# rfid_module.net
KiCad netlist of a schematic drawn in EAGLE
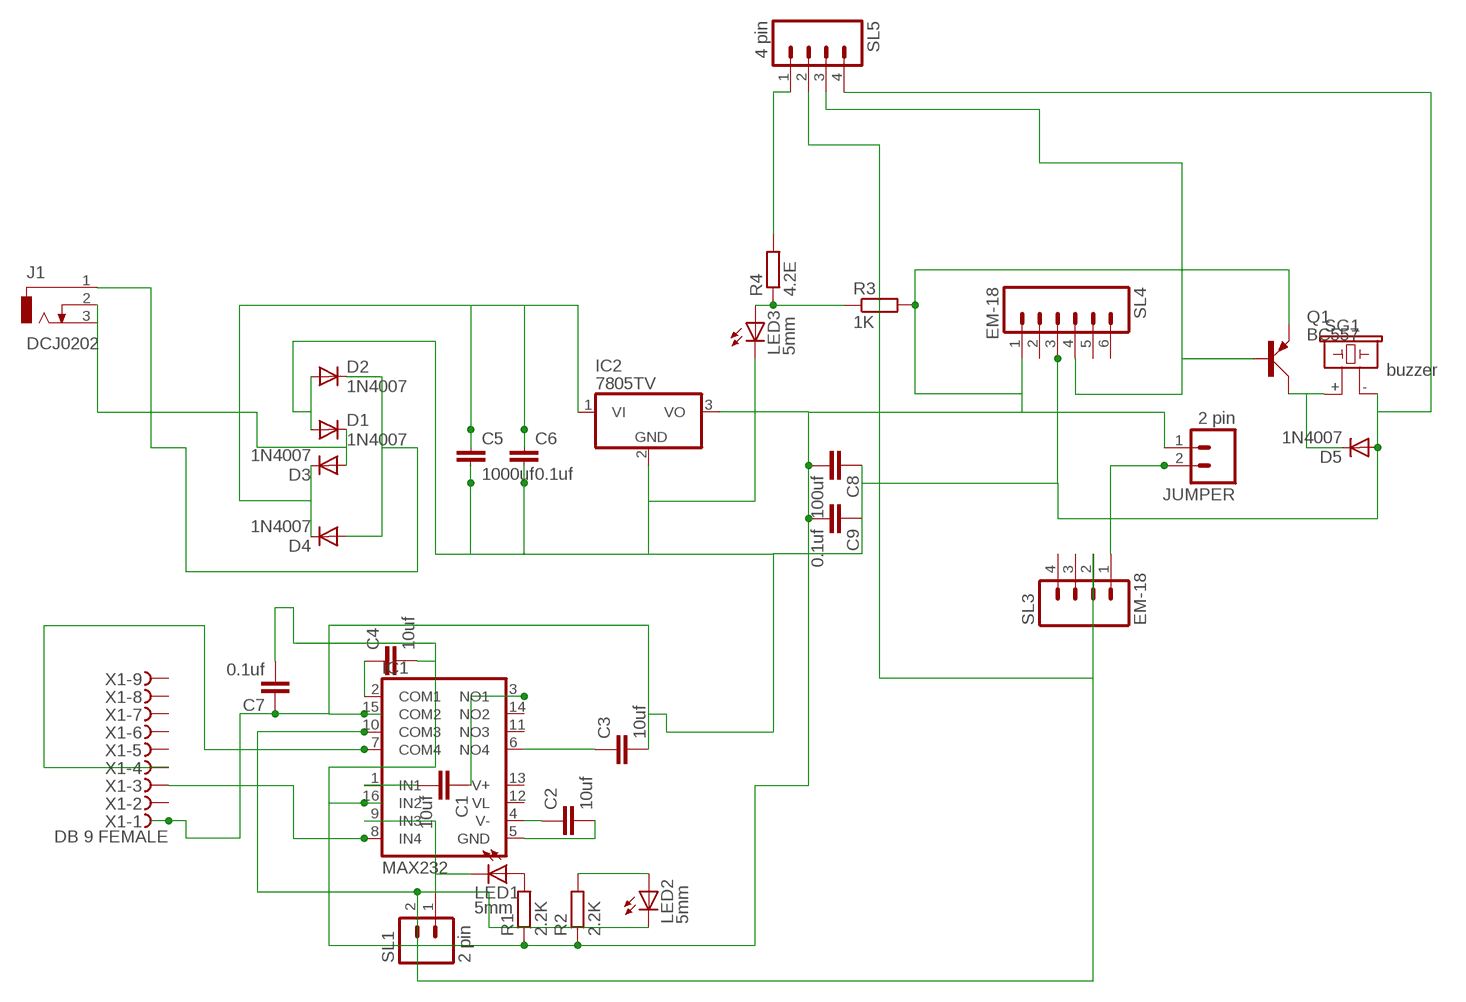
[diagram p0: schematic, sheet 1]

(export (version "E")
  (design (tool "Eeschema 10.0.6"))
  (components
    (comp (ref "C1")
      (value "10uf")
      (footprint "eagle-import:C2.5-3")
      (libsource (lib "eagle-import") (part "C2,5-3"))
    )
    (comp (ref "C2")
      (value "10uf")
      (footprint "eagle-import:C2.5-3")
      (libsource (lib "eagle-import") (part "C2,5-3"))
    )
    (comp (ref "C3")
      (value "10uf")
      (footprint "eagle-import:C2.5-3")
      (libsource (lib "eagle-import") (part "C2,5-3"))
    )
    (comp (ref "C4")
      (value "10uf")
      (footprint "eagle-import:C2.5-3")
      (libsource (lib "eagle-import") (part "C2,5-3"))
    )
    (comp (ref "C5")
      (value "1000uf")
      (footprint "eagle-import:C5B7.2")
      (libsource (lib "eagle-import") (part "C5/7.2"))
    )
    (comp (ref "C6")
      (value "0.1uf")
      (footprint "eagle-import:C2.5-3")
      (libsource (lib "eagle-import") (part "C2,5-3"))
    )
    (comp (ref "C7")
      (value "0.1uf")
      (footprint "eagle-import:C2.5-3")
      (libsource (lib "eagle-import") (part "C2,5-3"))
    )
    (comp (ref "C8")
      (value "100uf")
      (footprint "eagle-import:C2.5-3")
      (libsource (lib "eagle-import") (part "C2,5-3"))
    )
    (comp (ref "C9")
      (value "0.1uf")
      (footprint "eagle-import:C2.5-3")
      (libsource (lib "eagle-import") (part "C2,5-3"))
    )
    (comp (ref "D1")
      (value "1N4007")
      (footprint "eagle-import:DO41-10")
      (libsource (lib "eagle-import") (part "1N4004"))
    )
    (comp (ref "D2")
      (value "1N4007")
      (footprint "eagle-import:DO41-10")
      (libsource (lib "eagle-import") (part "1N4004"))
    )
    (comp (ref "D3")
      (value "1N4007")
      (footprint "eagle-import:DO41-10")
      (libsource (lib "eagle-import") (part "1N4004"))
    )
    (comp (ref "D4")
      (value "1N4007")
      (footprint "eagle-import:DO41-10")
      (libsource (lib "eagle-import") (part "1N4004"))
    )
    (comp (ref "D5")
      (value "1N4007")
      (footprint "eagle-import:DO41-10")
      (libsource (lib "eagle-import") (part "1N4004"))
    )
    (comp (ref "IC1")
      (value "MAX232")
      (footprint "eagle-import:DIL16")
      (fields (field (name "MPN") "MAX313EPE+"))
      (libsource (lib "eagle-import") (part "MAX313PEE"))
    )
    (comp (ref "IC2")
      (value "7805TV")
      (footprint "eagle-import:TO220V")
      (libsource (lib "eagle-import") (part "78TV05"))
    )
    (comp (ref "J1")
      (value "DCJ0202")
      (footprint "eagle-import:DCJ0202")
      (libsource (lib "eagle-import") (part "DCJ0202"))
    )
    (comp (ref "JUMPER")
      (value "2 pin")
      (footprint "eagle-import:02P")
      (libsource (lib "eagle-import") (part "M02"))
    )
    (comp (ref "LED1")
      (value "5mm")
      (footprint "eagle-import:LED5MM")
      (libsource (lib "eagle-import") (part "LED5MM"))
    )
    (comp (ref "LED2")
      (value "5mm")
      (footprint "eagle-import:LED5MM")
      (libsource (lib "eagle-import") (part "LED5MM"))
    )
    (comp (ref "LED3")
      (value "5mm")
      (footprint "eagle-import:LED5MM")
      (libsource (lib "eagle-import") (part "LED5MM"))
    )
    (comp (ref "Q1")
      (value "BC557")
      (footprint "eagle-import:SOT54A")
      (libsource (lib "eagle-import") (part "BC557"))
    )
    (comp (ref "R1")
      (value "2.2K")
      (footprint "eagle-import:0204_7")
      (libsource (lib "eagle-import") (part "R-EU_0204/7"))
    )
    (comp (ref "R2")
      (value "2.2K")
      (footprint "eagle-import:0204_7")
      (libsource (lib "eagle-import") (part "R-EU_0204/7"))
    )
    (comp (ref "R3")
      (value "1K")
      (footprint "eagle-import:0204_7")
      (libsource (lib "eagle-import") (part "R-EU_0204/7"))
    )
    (comp (ref "R4")
      (value "4.2E")
      (footprint "eagle-import:0204_7")
      (libsource (lib "eagle-import") (part "R-EU_0204/7"))
    )
    (comp (ref "SG1")
      (value "buzzer")
      (footprint "eagle-import:F_CM12P")
      (libsource (lib "eagle-import") (part "F/CM12P"))
    )
    (comp (ref "SL1")
      (value "2 pin")
      (footprint "eagle-import:02P")
      (libsource (lib "eagle-import") (part "M02"))
    )
    (comp (ref "SL3")
      (value "EM-18")
      (footprint "eagle-import:04P")
      (libsource (lib "eagle-import") (part "M04"))
    )
    (comp (ref "SL4")
      (value "EM-18")
      (footprint "eagle-import:06P")
      (libsource (lib "eagle-import") (part "M06"))
    )
    (comp (ref "SL5")
      (value "4 pin")
      (footprint "eagle-import:04P")
      (fields (field (name "OC_FARNELL") "unknown") (field (name "OC_NEWARK") "unknown"))
      (libsource (lib "eagle-import") (part "M04"))
    )
    (comp (ref "X1")
      (value "DB 9 FEMALE")
      (footprint "eagle-import:H2M09ST")
      (libsource (lib "eagle-import") (part "D-SUB9-H2M09ST"))
    )
  )
  (nets
    (net (code "1") (name "/V+") (class "Default")
      (node (ref "IC1") (pin "13") (pinfunction "V+_13") (pintype "power_in"))
    )
    (net (code "2") (name "/VL") (class "Default")
      (node (ref "IC1") (pin "12") (pinfunction "VL_12") (pintype "power_in"))
    )
    (net (code "3") (name "Net-(D1-PadC)") (class "Default")
      (node (ref "D1") (pin "C") (pinfunction "C_C") (pintype "passive"))
      (node (ref "D3") (pin "A") (pinfunction "A_A") (pintype "passive"))
      (node (ref "J1") (pin "2") (pinfunction "2_2") (pintype "passive"))
      (node (ref "J1") (pin "3") (pinfunction "3_3") (pintype "passive"))
    )
    (net (code "4") (name "Net-(D2-PadC)") (class "Default")
      (node (ref "D2") (pin "C") (pinfunction "C_C") (pintype "passive"))
      (node (ref "D4") (pin "A") (pinfunction "A_A") (pintype "passive"))
      (node (ref "J1") (pin "1") (pinfunction "1_1") (pintype "passive"))
    )
    (net (code "5") (name "Net-(IC1-COM1)") (class "Default")
      (node (ref "C4") (pin "1") (pinfunction "1_1") (pintype "passive"))
      (node (ref "IC1") (pin "2") (pinfunction "COM1_2") (pintype "passive"))
    )
    (net (code "6") (name "Net-(IC1-COM2)") (class "Default")
      (node (ref "C3") (pin "2") (pinfunction "2_2") (pintype "passive"))
      (node (ref "C5") (pin "2") (pinfunction "2_2") (pintype "passive"))
      (node (ref "C6") (pin "2") (pinfunction "2_2") (pintype "passive"))
      (node (ref "C7") (pin "1") (pinfunction "1_1") (pintype "passive"))
      (node (ref "C8") (pin "1") (pinfunction "1_1") (pintype "passive"))
      (node (ref "C9") (pin "1") (pinfunction "1_1") (pintype "passive"))
      (node (ref "D1") (pin "A") (pinfunction "A_A") (pintype "passive"))
      (node (ref "D2") (pin "A") (pinfunction "A_A") (pintype "passive"))
      (node (ref "D5") (pin "A") (pinfunction "A_A") (pintype "passive"))
      (node (ref "IC1") (pin "15") (pinfunction "COM2_15") (pintype "passive"))
      (node (ref "IC2") (pin "2") (pinfunction "GND_2") (pintype "passive"))
      (node (ref "LED3") (pin "K") (pinfunction "C_K") (pintype "passive"))
      (node (ref "SG1") (pin "-") (pinfunction "2_-") (pintype "passive"))
      (node (ref "SL4") (pin "3") (pinfunction "3_3") (pintype "passive"))
      (node (ref "SL5") (pin "4") (pinfunction "4_4") (pintype "passive"))
      (node (ref "X1") (pin "1") (pinfunction "F_1") (pintype "passive"))
    )
    (net (code "7") (name "Net-(IC1-COM3)") (class "Default")
      (node (ref "IC1") (pin "10") (pinfunction "COM3_10") (pintype "passive"))
      (node (ref "LED2") (pin "K") (pinfunction "C_K") (pintype "passive"))
      (node (ref "SL1") (pin "2") (pinfunction "2_2") (pintype "passive"))
      (node (ref "SL3") (pin "2") (pinfunction "2_2") (pintype "passive"))
      (node (ref "SL5") (pin "2") (pinfunction "2_2") (pintype "passive"))
    )
    (net (code "8") (name "Net-(IC1-COM4)") (class "Default")
      (node (ref "IC1") (pin "7") (pinfunction "COM4_7") (pintype "passive"))
      (node (ref "X1") (pin "4") (pinfunction "F_4") (pintype "passive"))
    )
    (net (code "9") (name "Net-(IC1-GND)") (class "Default")
      (node (ref "C2") (pin "2") (pinfunction "2_2") (pintype "passive"))
      (node (ref "IC1") (pin "5") (pinfunction "GND_5") (pintype "power_in"))
    )
    (net (code "10") (name "Net-(IC1-IN1)") (class "Default")
      (node (ref "C1") (pin "2") (pinfunction "2_2") (pintype "passive"))
      (node (ref "IC1") (pin "1") (pinfunction "IN1_1") (pintype "input"))
    )
    (net (code "11") (name "Net-(IC1-IN2)") (class "Default")
      (node (ref "C4") (pin "2") (pinfunction "2_2") (pintype "passive"))
      (node (ref "C7") (pin "2") (pinfunction "2_2") (pintype "passive"))
      (node (ref "C8") (pin "2") (pinfunction "2_2") (pintype "passive"))
      (node (ref "C9") (pin "2") (pinfunction "2_2") (pintype "passive"))
      (node (ref "IC1") (pin "16") (pinfunction "IN2_16") (pintype "input"))
      (node (ref "IC2") (pin "3") (pinfunction "VO_3") (pintype "passive"))
      (node (ref "JUMPER") (pin "1") (pinfunction "1_1") (pintype "passive"))
      (node (ref "Q1") (pin "E") (pinfunction "E_E") (pintype "passive"))
      (node (ref "R1") (pin "1") (pinfunction "1_1") (pintype "passive"))
      (node (ref "R2") (pin "1") (pinfunction "1_1") (pintype "passive"))
      (node (ref "R3") (pin "2") (pinfunction "2_2") (pintype "passive"))
      (node (ref "SL4") (pin "1") (pinfunction "1_1") (pintype "passive"))
    )
    (net (code "12") (name "Net-(IC1-IN3)") (class "Default")
      (node (ref "IC1") (pin "9") (pinfunction "IN3_9") (pintype "input"))
      (node (ref "LED1") (pin "K") (pinfunction "C_K") (pintype "passive"))
      (node (ref "SL1") (pin "1") (pinfunction "1_1") (pintype "passive"))
    )
    (net (code "13") (name "Net-(IC1-IN4)") (class "Default")
      (node (ref "IC1") (pin "8") (pinfunction "IN4_8") (pintype "input"))
      (node (ref "X1") (pin "3") (pinfunction "F_3") (pintype "passive"))
    )
    (net (code "14") (name "Net-(IC1-NO1)") (class "Default")
      (node (ref "C1") (pin "1") (pinfunction "1_1") (pintype "passive"))
      (node (ref "IC1") (pin "3") (pinfunction "NO1_3") (pintype "passive"))
    )
    (net (code "15") (name "Net-(IC1-NO4)") (class "Default")
      (node (ref "C3") (pin "1") (pinfunction "1_1") (pintype "passive"))
      (node (ref "IC1") (pin "6") (pinfunction "NO4_6") (pintype "passive"))
    )
    (net (code "16") (name "Net-(IC1-V-)") (class "Default")
      (node (ref "C2") (pin "1") (pinfunction "1_1") (pintype "passive"))
      (node (ref "IC1") (pin "4") (pinfunction "V-_4") (pintype "power_in"))
    )
    (net (code "17") (name "Net-(IC2-VI)") (class "Default")
      (node (ref "C5") (pin "1") (pinfunction "1_1") (pintype "passive"))
      (node (ref "C6") (pin "1") (pinfunction "1_1") (pintype "passive"))
      (node (ref "D3") (pin "C") (pinfunction "C_C") (pintype "passive"))
      (node (ref "D4") (pin "C") (pinfunction "C_C") (pintype "passive"))
      (node (ref "IC2") (pin "1") (pinfunction "VI_1") (pintype "input"))
    )
    (net (code "18") (name "Net-(JUMPER-Pad2)") (class "Default")
      (node (ref "JUMPER") (pin "2") (pinfunction "2_2") (pintype "passive"))
      (node (ref "SL3") (pin "1") (pinfunction "1_1") (pintype "passive"))
    )
    (net (code "19") (name "Net-(LED1-PadA)") (class "Default")
      (node (ref "LED1") (pin "A") (pinfunction "A_A") (pintype "passive"))
      (node (ref "R1") (pin "2") (pinfunction "2_2") (pintype "passive"))
    )
    (net (code "20") (name "Net-(LED2-PadA)") (class "Default")
      (node (ref "LED2") (pin "A") (pinfunction "A_A") (pintype "passive"))
      (node (ref "R2") (pin "2") (pinfunction "2_2") (pintype "passive"))
    )
    (net (code "21") (name "Net-(LED3-PadA)") (class "Default")
      (node (ref "LED3") (pin "A") (pinfunction "A_A") (pintype "passive"))
      (node (ref "R3") (pin "1") (pinfunction "1_1") (pintype "passive"))
      (node (ref "R4") (pin "1") (pinfunction "1_1") (pintype "passive"))
    )
    (net (code "22") (name "Net-(Q1-PadB)") (class "Default")
      (node (ref "Q1") (pin "B") (pinfunction "B_B") (pintype "passive"))
      (node (ref "SL4") (pin "4") (pinfunction "4_4") (pintype "passive"))
      (node (ref "SL5") (pin "3") (pinfunction "3_3") (pintype "passive"))
    )
    (net (code "23") (name "Net-(R4-Pad2)") (class "Default")
      (node (ref "R4") (pin "2") (pinfunction "2_2") (pintype "passive"))
      (node (ref "SL5") (pin "1") (pinfunction "1_1") (pintype "passive"))
    )
    (net (code "24") (name "Net-(SG1-1)") (class "Default")
      (node (ref "D5") (pin "C") (pinfunction "C_C") (pintype "passive"))
      (node (ref "Q1") (pin "C") (pinfunction "C_C") (pintype "passive"))
      (node (ref "SG1") (pin "+") (pinfunction "1_+") (pintype "passive"))
    )
    (net (code "25") (name "unconnected-(IC1-NO2-Pad14)") (class "Default")
      (node (ref "IC1") (pin "14") (pinfunction "NO2_14") (pintype "passive"))
    )
    (net (code "26") (name "unconnected-(IC1-NO3-Pad11)") (class "Default")
      (node (ref "IC1") (pin "11") (pinfunction "NO3_11") (pintype "passive"))
    )
    (net (code "27") (name "unconnected-(SL3-Pad3)") (class "Default")
      (node (ref "SL3") (pin "3") (pinfunction "3_3") (pintype "passive"))
    )
    (net (code "28") (name "unconnected-(SL3-Pad4)") (class "Default")
      (node (ref "SL3") (pin "4") (pinfunction "4_4") (pintype "passive"))
    )
    (net (code "29") (name "unconnected-(SL4-Pad2)") (class "Default")
      (node (ref "SL4") (pin "2") (pinfunction "2_2") (pintype "passive"))
    )
    (net (code "30") (name "unconnected-(SL4-Pad5)") (class "Default")
      (node (ref "SL4") (pin "5") (pinfunction "5_5") (pintype "passive"))
    )
    (net (code "31") (name "unconnected-(SL4-Pad6)") (class "Default")
      (node (ref "SL4") (pin "6") (pinfunction "6_6") (pintype "passive"))
    )
    (net (code "32") (name "unconnected-(X1B-F-Pad2)") (class "Default")
      (node (ref "X1") (pin "2") (pinfunction "F_2") (pintype "passive"))
    )
    (net (code "33") (name "unconnected-(X1E-F-Pad5)") (class "Default")
      (node (ref "X1") (pin "5") (pinfunction "F_5") (pintype "passive"))
    )
    (net (code "34") (name "unconnected-(X1F-F-Pad6)") (class "Default")
      (node (ref "X1") (pin "6") (pinfunction "F_6") (pintype "passive"))
    )
    (net (code "35") (name "unconnected-(X1G-F-Pad7)") (class "Default")
      (node (ref "X1") (pin "7") (pinfunction "F_7") (pintype "passive"))
    )
    (net (code "36") (name "unconnected-(X1H-F-Pad8)") (class "Default")
      (node (ref "X1") (pin "8") (pinfunction "F_8") (pintype "passive"))
    )
    (net (code "37") (name "unconnected-(X1I-F-Pad9)") (class "Default")
      (node (ref "X1") (pin "9") (pinfunction "F_9") (pintype "passive"))
    )
  )
)
